# Low-Frequency-LC-Oscillator.net
KiCad netlist of a schematic drawn in EAGLE
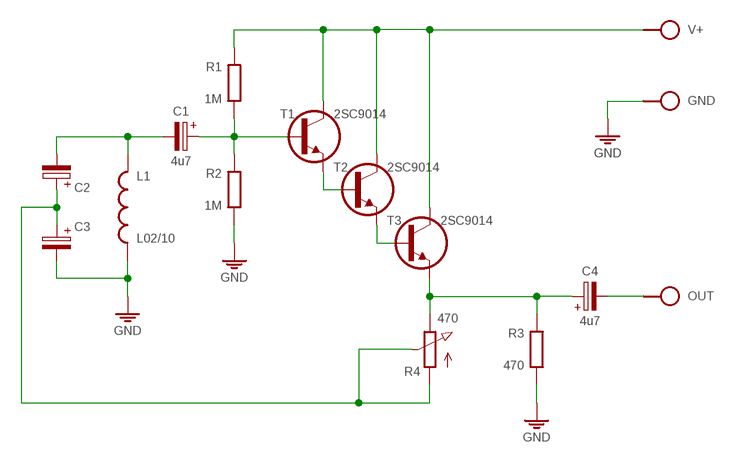
[diagram p0: schematic, sheet 1]

(export (version "E")
  (design (tool "Eeschema 10.0.6"))
  (components
    (comp (ref "C1")
      (value "4u7")
      (footprint "eagle-import:E2,5-3")
      (libsource (lib "eagle-import") (part "CPOLE2,5-3"))
    )
    (comp (ref "C2")
      (value "CPOLE2.5-5")
      (footprint "eagle-import:E2,5-5")
      (libsource (lib "eagle-import") (part "CPOLE2.5-5"))
    )
    (comp (ref "C3")
      (value "CPOLE2.5-5")
      (footprint "eagle-import:E2,5-5")
      (libsource (lib "eagle-import") (part "CPOLE2.5-5"))
    )
    (comp (ref "C4")
      (value "4u7")
      (footprint "eagle-import:E2,5-3")
      (libsource (lib "eagle-import") (part "CPOLE2,5-3"))
    )
    (comp (ref "GND")
      (value "SPAD")
      (footprint "eagle-import:SPAD")
      (libsource (lib "eagle-import") (part "SPAD"))
    )
    (comp (ref "L1")
      (value "L02/10")
      (footprint "eagle-import:L-03_10V")
      (libsource (lib "eagle-import") (part "L02/10"))
    )
    (comp (ref "OUT")
      (value "SPAD")
      (footprint "eagle-import:SPAD")
      (libsource (lib "eagle-import") (part "SPAD"))
    )
    (comp (ref "R1")
      (value "1M")
      (footprint "eagle-import:0204_10")
      (libsource (lib "eagle-import") (part "R0204/10"))
    )
    (comp (ref "R2")
      (value "1M")
      (footprint "eagle-import:0204_10")
      (libsource (lib "eagle-import") (part "R0204/10"))
    )
    (comp (ref "R3")
      (value "470")
      (footprint "eagle-import:0204_10")
      (libsource (lib "eagle-import") (part "R0204/10"))
    )
    (comp (ref "R4")
      (value "470")
      (footprint "eagle-import:POT")
      (libsource (lib "eagle-import") (part "POT"))
    )
    (comp (ref "T1")
      (value "2SC9014")
      (footprint "eagle-import:TO92-EBC")
      (libsource (lib "eagle-import") (part "2SC9014"))
    )
    (comp (ref "T2")
      (value "2SC9014")
      (footprint "eagle-import:TO92-EBC")
      (libsource (lib "eagle-import") (part "2SC9014"))
    )
    (comp (ref "T3")
      (value "2SC9014")
      (footprint "eagle-import:TO92-EBC")
      (libsource (lib "eagle-import") (part "2SC9014"))
    )
    (comp (ref "V+")
      (value "SPAD")
      (footprint "eagle-import:SPAD")
      (libsource (lib "eagle-import") (part "SPAD"))
    )
  )
  (nets
    (net (code "1") (name "GND") (class "Default")
      (node (ref "C3") (pin "-") (pinfunction "-_-") (pintype "passive"))
      (node (ref "GND") (pin "1") (pinfunction "P$1_1") (pintype "bidirectional"))
      (node (ref "L1") (pin "2") (pinfunction "2_2") (pintype "passive"))
      (node (ref "R2") (pin "1") (pinfunction "1_1") (pintype "passive"))
      (node (ref "R3") (pin "1") (pinfunction "1_1") (pintype "passive"))
    )
    (net (code "2") (name "Net-(C1-Pad+)") (class "Default")
      (node (ref "C1") (pin "+") (pinfunction "+_+") (pintype "passive"))
      (node (ref "R1") (pin "1") (pinfunction "1_1") (pintype "passive"))
      (node (ref "R2") (pin "2") (pinfunction "2_2") (pintype "passive"))
      (node (ref "T1") (pin "B") (pinfunction "B_B") (pintype "passive"))
    )
    (net (code "3") (name "Net-(C1-Pad-)") (class "Default")
      (node (ref "C1") (pin "-") (pinfunction "-_-") (pintype "passive"))
      (node (ref "C2") (pin "-") (pinfunction "-_-") (pintype "passive"))
      (node (ref "L1") (pin "1") (pinfunction "1_1") (pintype "passive"))
    )
    (net (code "4") (name "Net-(OUT-P$1)") (class "Default")
      (node (ref "C4") (pin "-") (pinfunction "-_-") (pintype "passive"))
      (node (ref "OUT") (pin "1") (pinfunction "P$1_1") (pintype "bidirectional"))
    )
    (net (code "5") (name "Net-(R4-A)") (class "Default")
      (node (ref "C2") (pin "+") (pinfunction "+_+") (pintype "passive"))
      (node (ref "C3") (pin "+") (pinfunction "+_+") (pintype "passive"))
      (node (ref "R4") (pin "1") (pinfunction "A_1") (pintype "passive"))
      (node (ref "R4") (pin "2") (pinfunction "S_2") (pintype "passive"))
    )
    (net (code "6") (name "Net-(R4-E)") (class "Default")
      (node (ref "C4") (pin "+") (pinfunction "+_+") (pintype "passive"))
      (node (ref "R3") (pin "2") (pinfunction "2_2") (pintype "passive"))
      (node (ref "R4") (pin "3") (pinfunction "E_3") (pintype "passive"))
      (node (ref "T3") (pin "E") (pinfunction "E_E") (pintype "passive"))
    )
    (net (code "7") (name "Net-(T1-PadE)") (class "Default")
      (node (ref "T1") (pin "E") (pinfunction "E_E") (pintype "passive"))
      (node (ref "T2") (pin "B") (pinfunction "B_B") (pintype "passive"))
    )
    (net (code "8") (name "Net-(T2-PadE)") (class "Default")
      (node (ref "T2") (pin "E") (pinfunction "E_E") (pintype "passive"))
      (node (ref "T3") (pin "B") (pinfunction "B_B") (pintype "passive"))
    )
    (net (code "9") (name "Net-(V+-P$1)") (class "Default")
      (node (ref "R1") (pin "2") (pinfunction "2_2") (pintype "passive"))
      (node (ref "T1") (pin "C") (pinfunction "C_C") (pintype "passive"))
      (node (ref "T2") (pin "C") (pinfunction "C_C") (pintype "passive"))
      (node (ref "T3") (pin "C") (pinfunction "C_C") (pintype "passive"))
      (node (ref "V+") (pin "1") (pinfunction "P$1_1") (pintype "bidirectional"))
    )
  )
)
